# QRD.net
KiCad netlist of a schematic drawn in EAGLE
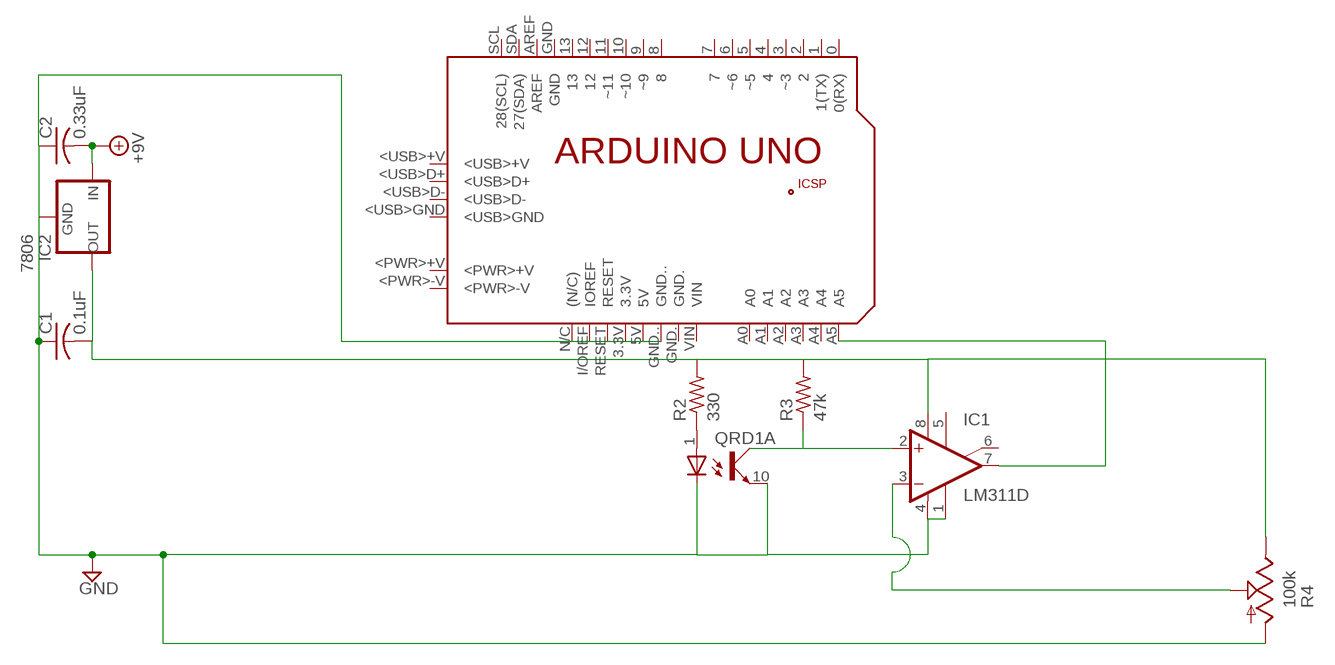
[diagram p0: schematic, sheet 1]

(export (version "E")
  (design (tool "Eeschema 10.0.6"))
  (components
    (comp (ref "C1")
      (value "0.1uF")
      (footprint "eagle-import:C025-024X044")
      (libsource (lib "eagle-import") (part "C-US025-024X044"))
    )
    (comp (ref "C2")
      (value "0.33uF")
      (footprint "eagle-import:C025-024X044")
      (libsource (lib "eagle-import") (part "C-US025-024X044"))
    )
    (comp (ref "IC1")
      (value "LM311D")
      (footprint "eagle-import:SO08")
      (libsource (lib "eagle-import") (part "LM311D"))
    )
    (comp (ref "IC2")
      (value "7806")
      (footprint "eagle-import:78XXL")
      (libsource (lib "eagle-import") (part "78XXL"))
    )
    (comp (ref "PCB1")
      (value "ARDUINO_UNO")
      (footprint "eagle-import:ARDUINO_UNO")
      (libsource (lib "eagle-import") (part "ARDUINO_UNO"))
    )
    (comp (ref "QRD1")
      (value "SFH6943")
      (footprint "eagle-import:SOT223_10")
      (fields (field (name "MPN") "SFH6943A-4T"))
      (libsource (lib "eagle-import") (part "SFH6943"))
    )
    (comp (ref "R2")
      (value "330")
      (footprint "eagle-import:0204V")
      (libsource (lib "eagle-import") (part "R-US_0204/2V"))
    )
    (comp (ref "R3")
      (value "47k")
      (footprint "eagle-import:0204V")
      (libsource (lib "eagle-import") (part "R-US_0204/2V"))
    )
    (comp (ref "R4")
      (value "100k")
      (footprint "eagle-import:3223G")
      (libsource (lib "eagle-import") (part "TRIM_US-3223G"))
    )
  )
  (nets
    (net (code "1") (name "+9V") (class "Default")
      (node (ref "C2") (pin "2") (pinfunction "2_2") (pintype "passive"))
      (node (ref "IC2") (pin "IN") (pinfunction "IN_IN") (pintype "input"))
    )
    (net (code "2") (name "GND") (class "Default")
      (node (ref "C1") (pin "1") (pinfunction "1_1") (pintype "passive"))
      (node (ref "C2") (pin "1") (pinfunction "1_1") (pintype "passive"))
      (node (ref "IC1") (pin "1") (pinfunction "GND_1") (pintype "passive"))
      (node (ref "IC1") (pin "4") (pinfunction "V-_4") (pintype "power_in"))
      (node (ref "IC2") (pin "GND") (pinfunction "GND_GND") (pintype "input"))
      (node (ref "PCB1") (pin "GND..") (pinfunction "GND.._GND..") (pintype "bidirectional"))
      (node (ref "QRD1") (pin "10") (pinfunction "EMI_10") (pintype "passive"))
      (node (ref "R4") (pin "1") (pinfunction "A_1") (pintype "passive"))
    )
    (net (code "3") (name "Net-(IC1-+IN)") (class "Default")
      (node (ref "IC1") (pin "2") (pinfunction "+IN_2") (pintype "input"))
      (node (ref "R3") (pin "1") (pinfunction "1_1") (pintype "passive"))
    )
    (net (code "4") (name "Net-(IC1--IN)") (class "Default")
      (node (ref "IC1") (pin "3") (pinfunction "-IN_3") (pintype "input"))
      (node (ref "R4") (pin "2") (pinfunction "S_2") (pintype "passive"))
    )
    (net (code "5") (name "Net-(IC1-OUT)") (class "Default")
      (node (ref "IC1") (pin "7") (pinfunction "OUT_7") (pintype "output"))
      (node (ref "PCB1") (pin "A5") (pinfunction "A5_A5") (pintype "bidirectional"))
    )
    (net (code "6") (name "Net-(IC1-V+)") (class "Default")
      (node (ref "C1") (pin "2") (pinfunction "2_2") (pintype "passive"))
      (node (ref "IC1") (pin "8") (pinfunction "V+_8") (pintype "power_in"))
      (node (ref "IC2") (pin "OUT") (pinfunction "OUT_OUT") (pintype "passive"))
      (node (ref "R2") (pin "2") (pinfunction "2_2") (pintype "passive"))
      (node (ref "R3") (pin "2") (pinfunction "2_2") (pintype "passive"))
      (node (ref "R4") (pin "3") (pinfunction "E_3") (pintype "passive"))
    )
    (net (code "7") (name "Net-(QRD1A-A)") (class "Default")
      (node (ref "QRD1") (pin "1") (pinfunction "A_1") (pintype "passive"))
      (node (ref "R2") (pin "1") (pinfunction "1_1") (pintype "passive"))
    )
    (net (code "8") (name "unconnected-(IC1-ON-Pad5)") (class "Default")
      (node (ref "IC1") (pin "5") (pinfunction "ON_5") (pintype "passive"))
    )
    (net (code "9") (name "unconnected-(IC1-ON{slash}STR-Pad6)") (class "Default")
      (node (ref "IC1") (pin "6") (pinfunction "ON/STR_6") (pintype "passive"))
    )
    (net (code "10") (name "unconnected-(PCB1-(N{slash}C)-PadN{slash}C)") (class "Default")
      (node (ref "PCB1") (pin "N/C") (pinfunction "(N/C)_N/C") (pintype "bidirectional"))
    )
    (net (code "11") (name "unconnected-(PCB1-0(RX)-Pad0)") (class "Default")
      (node (ref "PCB1") (pin "0") (pinfunction "0(RX)_0") (pintype "bidirectional"))
    )
    (net (code "12") (name "unconnected-(PCB1-1(TX)-Pad1)") (class "Default")
      (node (ref "PCB1") (pin "1") (pinfunction "1(TX)_1") (pintype "bidirectional"))
    )
    (net (code "13") (name "unconnected-(PCB1-27(SDA)-PadSDA)") (class "Default")
      (node (ref "PCB1") (pin "SDA") (pinfunction "27(SDA)_SDA") (pintype "bidirectional"))
    )
    (net (code "14") (name "unconnected-(PCB1-28(SCL)-PadSCL)") (class "Default")
      (node (ref "PCB1") (pin "SCL") (pinfunction "28(SCL)_SCL") (pintype "bidirectional"))
    )
    (net (code "15") (name "unconnected-(PCB1-IOREF-PadI{slash}OREF)") (class "Default")
      (node (ref "PCB1") (pin "I/OREF") (pinfunction "IOREF_I/OREF") (pintype "bidirectional"))
    )
    (net (code "16") (name "unconnected-(PCB1-Pad+5V)") (class "Default")
      (node (ref "PCB1") (pin "+5V") (pinfunction "+5V_+5V") (pintype "bidirectional"))
    )
    (net (code "17") (name "unconnected-(PCB1-Pad2)") (class "Default")
      (node (ref "PCB1") (pin "2") (pinfunction "2_2") (pintype "bidirectional"))
    )
    (net (code "18") (name "unconnected-(PCB1-Pad3.3V)") (class "Default")
      (node (ref "PCB1") (pin "3.3V") (pinfunction "3.3V_3.3V") (pintype "bidirectional"))
    )
    (net (code "19") (name "unconnected-(PCB1-Pad4)") (class "Default")
      (node (ref "PCB1") (pin "4") (pinfunction "4_4") (pintype "bidirectional"))
    )
    (net (code "20") (name "unconnected-(PCB1-Pad5V)") (class "Default")
      (node (ref "PCB1") (pin "5V") (pinfunction "5V_5V") (pintype "bidirectional"))
    )
    (net (code "21") (name "unconnected-(PCB1-Pad7)") (class "Default")
      (node (ref "PCB1") (pin "7") (pinfunction "7_7") (pintype "bidirectional"))
    )
    (net (code "22") (name "unconnected-(PCB1-Pad8)") (class "Default")
      (node (ref "PCB1") (pin "8") (pinfunction "8_8") (pintype "bidirectional"))
    )
    (net (code "23") (name "unconnected-(PCB1-Pad12)") (class "Default")
      (node (ref "PCB1") (pin "12") (pinfunction "12_12") (pintype "bidirectional"))
    )
    (net (code "24") (name "unconnected-(PCB1-Pad13)") (class "Default")
      (node (ref "PCB1") (pin "13") (pinfunction "13_13") (pintype "bidirectional"))
    )
    (net (code "25") (name "unconnected-(PCB1-Pad<PWR>+V)") (class "Default")
      (node (ref "PCB1") (pin "<PWR>+V") (pinfunction "<PWR>+V_<PWR>+V") (pintype "bidirectional"))
    )
    (net (code "26") (name "unconnected-(PCB1-Pad<PWR>-V)") (class "Default")
      (node (ref "PCB1") (pin "<PWR>-V") (pinfunction "<PWR>-V_<PWR>-V") (pintype "bidirectional"))
    )
    (net (code "27") (name "unconnected-(PCB1-Pad<USB>+V)") (class "Default")
      (node (ref "PCB1") (pin "<USB>+V") (pinfunction "<USB>+V_<USB>+V") (pintype "bidirectional"))
    )
    (net (code "28") (name "unconnected-(PCB1-Pad<USB>D+)") (class "Default")
      (node (ref "PCB1") (pin "<USB>D+") (pinfunction "<USB>D+_<USB>D+") (pintype "bidirectional"))
    )
    (net (code "29") (name "unconnected-(PCB1-Pad<USB>D-)") (class "Default")
      (node (ref "PCB1") (pin "<USB>D-") (pinfunction "<USB>D-_<USB>D-") (pintype "bidirectional"))
    )
    (net (code "30") (name "unconnected-(PCB1-Pad<USB>GND)") (class "Default")
      (node (ref "PCB1") (pin "<USB>GND") (pinfunction "<USB>GND_<USB>GND") (pintype "bidirectional"))
    )
    (net (code "31") (name "unconnected-(PCB1-PadA0)") (class "Default")
      (node (ref "PCB1") (pin "A0") (pinfunction "A0_A0") (pintype "bidirectional"))
    )
    (net (code "32") (name "unconnected-(PCB1-PadA1)") (class "Default")
      (node (ref "PCB1") (pin "A1") (pinfunction "A1_A1") (pintype "bidirectional"))
    )
    (net (code "33") (name "unconnected-(PCB1-PadA2)") (class "Default")
      (node (ref "PCB1") (pin "A2") (pinfunction "A2_A2") (pintype "bidirectional"))
    )
    (net (code "34") (name "unconnected-(PCB1-PadA3)") (class "Default")
      (node (ref "PCB1") (pin "A3") (pinfunction "A3_A3") (pintype "bidirectional"))
    )
    (net (code "35") (name "unconnected-(PCB1-PadA4)") (class "Default")
      (node (ref "PCB1") (pin "A4") (pinfunction "A4_A4") (pintype "bidirectional"))
    )
    (net (code "36") (name "unconnected-(PCB1-PadAREF)") (class "Default")
      (node (ref "PCB1") (pin "AREF") (pinfunction "AREF_AREF") (pintype "bidirectional"))
    )
    (net (code "37") (name "unconnected-(PCB1-PadGND)") (class "Default")
      (node (ref "PCB1") (pin "GND") (pinfunction "GND_GND") (pintype "bidirectional"))
    )
    (net (code "38") (name "unconnected-(PCB1-PadGND.)") (class "Default")
      (node (ref "PCB1") (pin "GND.") (pinfunction "GND._GND.") (pintype "bidirectional"))
    )
    (net (code "39") (name "unconnected-(PCB1-PadGND_)") (class "Default")
      (node (ref "PCB1") (pin "GND_") (pinfunction "GND__GND_") (pintype "bidirectional"))
    )
    (net (code "40") (name "unconnected-(PCB1-PadMISO)") (class "Default")
      (node (ref "PCB1") (pin "MISO") (pinfunction "MISO_MISO") (pintype "bidirectional"))
    )
    (net (code "41") (name "unconnected-(PCB1-PadMOSI)") (class "Default")
      (node (ref "PCB1") (pin "MOSI") (pinfunction "MOSI_MOSI") (pintype "bidirectional"))
    )
    (net (code "42") (name "unconnected-(PCB1-PadRESET)") (class "Default")
      (node (ref "PCB1") (pin "RESET") (pinfunction "RESET_RESET") (pintype "bidirectional"))
    )
    (net (code "43") (name "unconnected-(PCB1-PadRESET.)") (class "Default")
      (node (ref "PCB1") (pin "RESET.") (pinfunction "RESET._RESET.") (pintype "bidirectional"))
    )
    (net (code "44") (name "unconnected-(PCB1-PadSCK)") (class "Default")
      (node (ref "PCB1") (pin "SCK") (pinfunction "SCK_SCK") (pintype "bidirectional"))
    )
    (net (code "45") (name "unconnected-(PCB1-PadVIN)") (class "Default")
      (node (ref "PCB1") (pin "VIN") (pinfunction "VIN_VIN") (pintype "bidirectional"))
    )
    (net (code "46") (name "unconnected-(PCB1-~{3}-Pad3)") (class "Default")
      (node (ref "PCB1") (pin "3") (pinfunction "~{3}_3") (pintype "bidirectional"))
    )
    (net (code "47") (name "unconnected-(PCB1-~{5}-Pad5)") (class "Default")
      (node (ref "PCB1") (pin "5") (pinfunction "~{5}_5") (pintype "bidirectional"))
    )
    (net (code "48") (name "unconnected-(PCB1-~{6}-Pad6)") (class "Default")
      (node (ref "PCB1") (pin "6") (pinfunction "~{6}_6") (pintype "bidirectional"))
    )
    (net (code "49") (name "unconnected-(PCB1-~{9}-Pad9)") (class "Default")
      (node (ref "PCB1") (pin "9") (pinfunction "~{9}_9") (pintype "bidirectional"))
    )
    (net (code "50") (name "unconnected-(PCB1-~{10}-Pad10)") (class "Default")
      (node (ref "PCB1") (pin "10") (pinfunction "~{10}_10") (pintype "bidirectional"))
    )
    (net (code "51") (name "unconnected-(PCB1-~{11}-Pad11)") (class "Default")
      (node (ref "PCB1") (pin "11") (pinfunction "~{11}_11") (pintype "bidirectional"))
    )
  )
)
